# ESP32_MusicBox_using_Modules_2021-03-20.net
KiCad netlist of a schematic drawn in EasyEDA
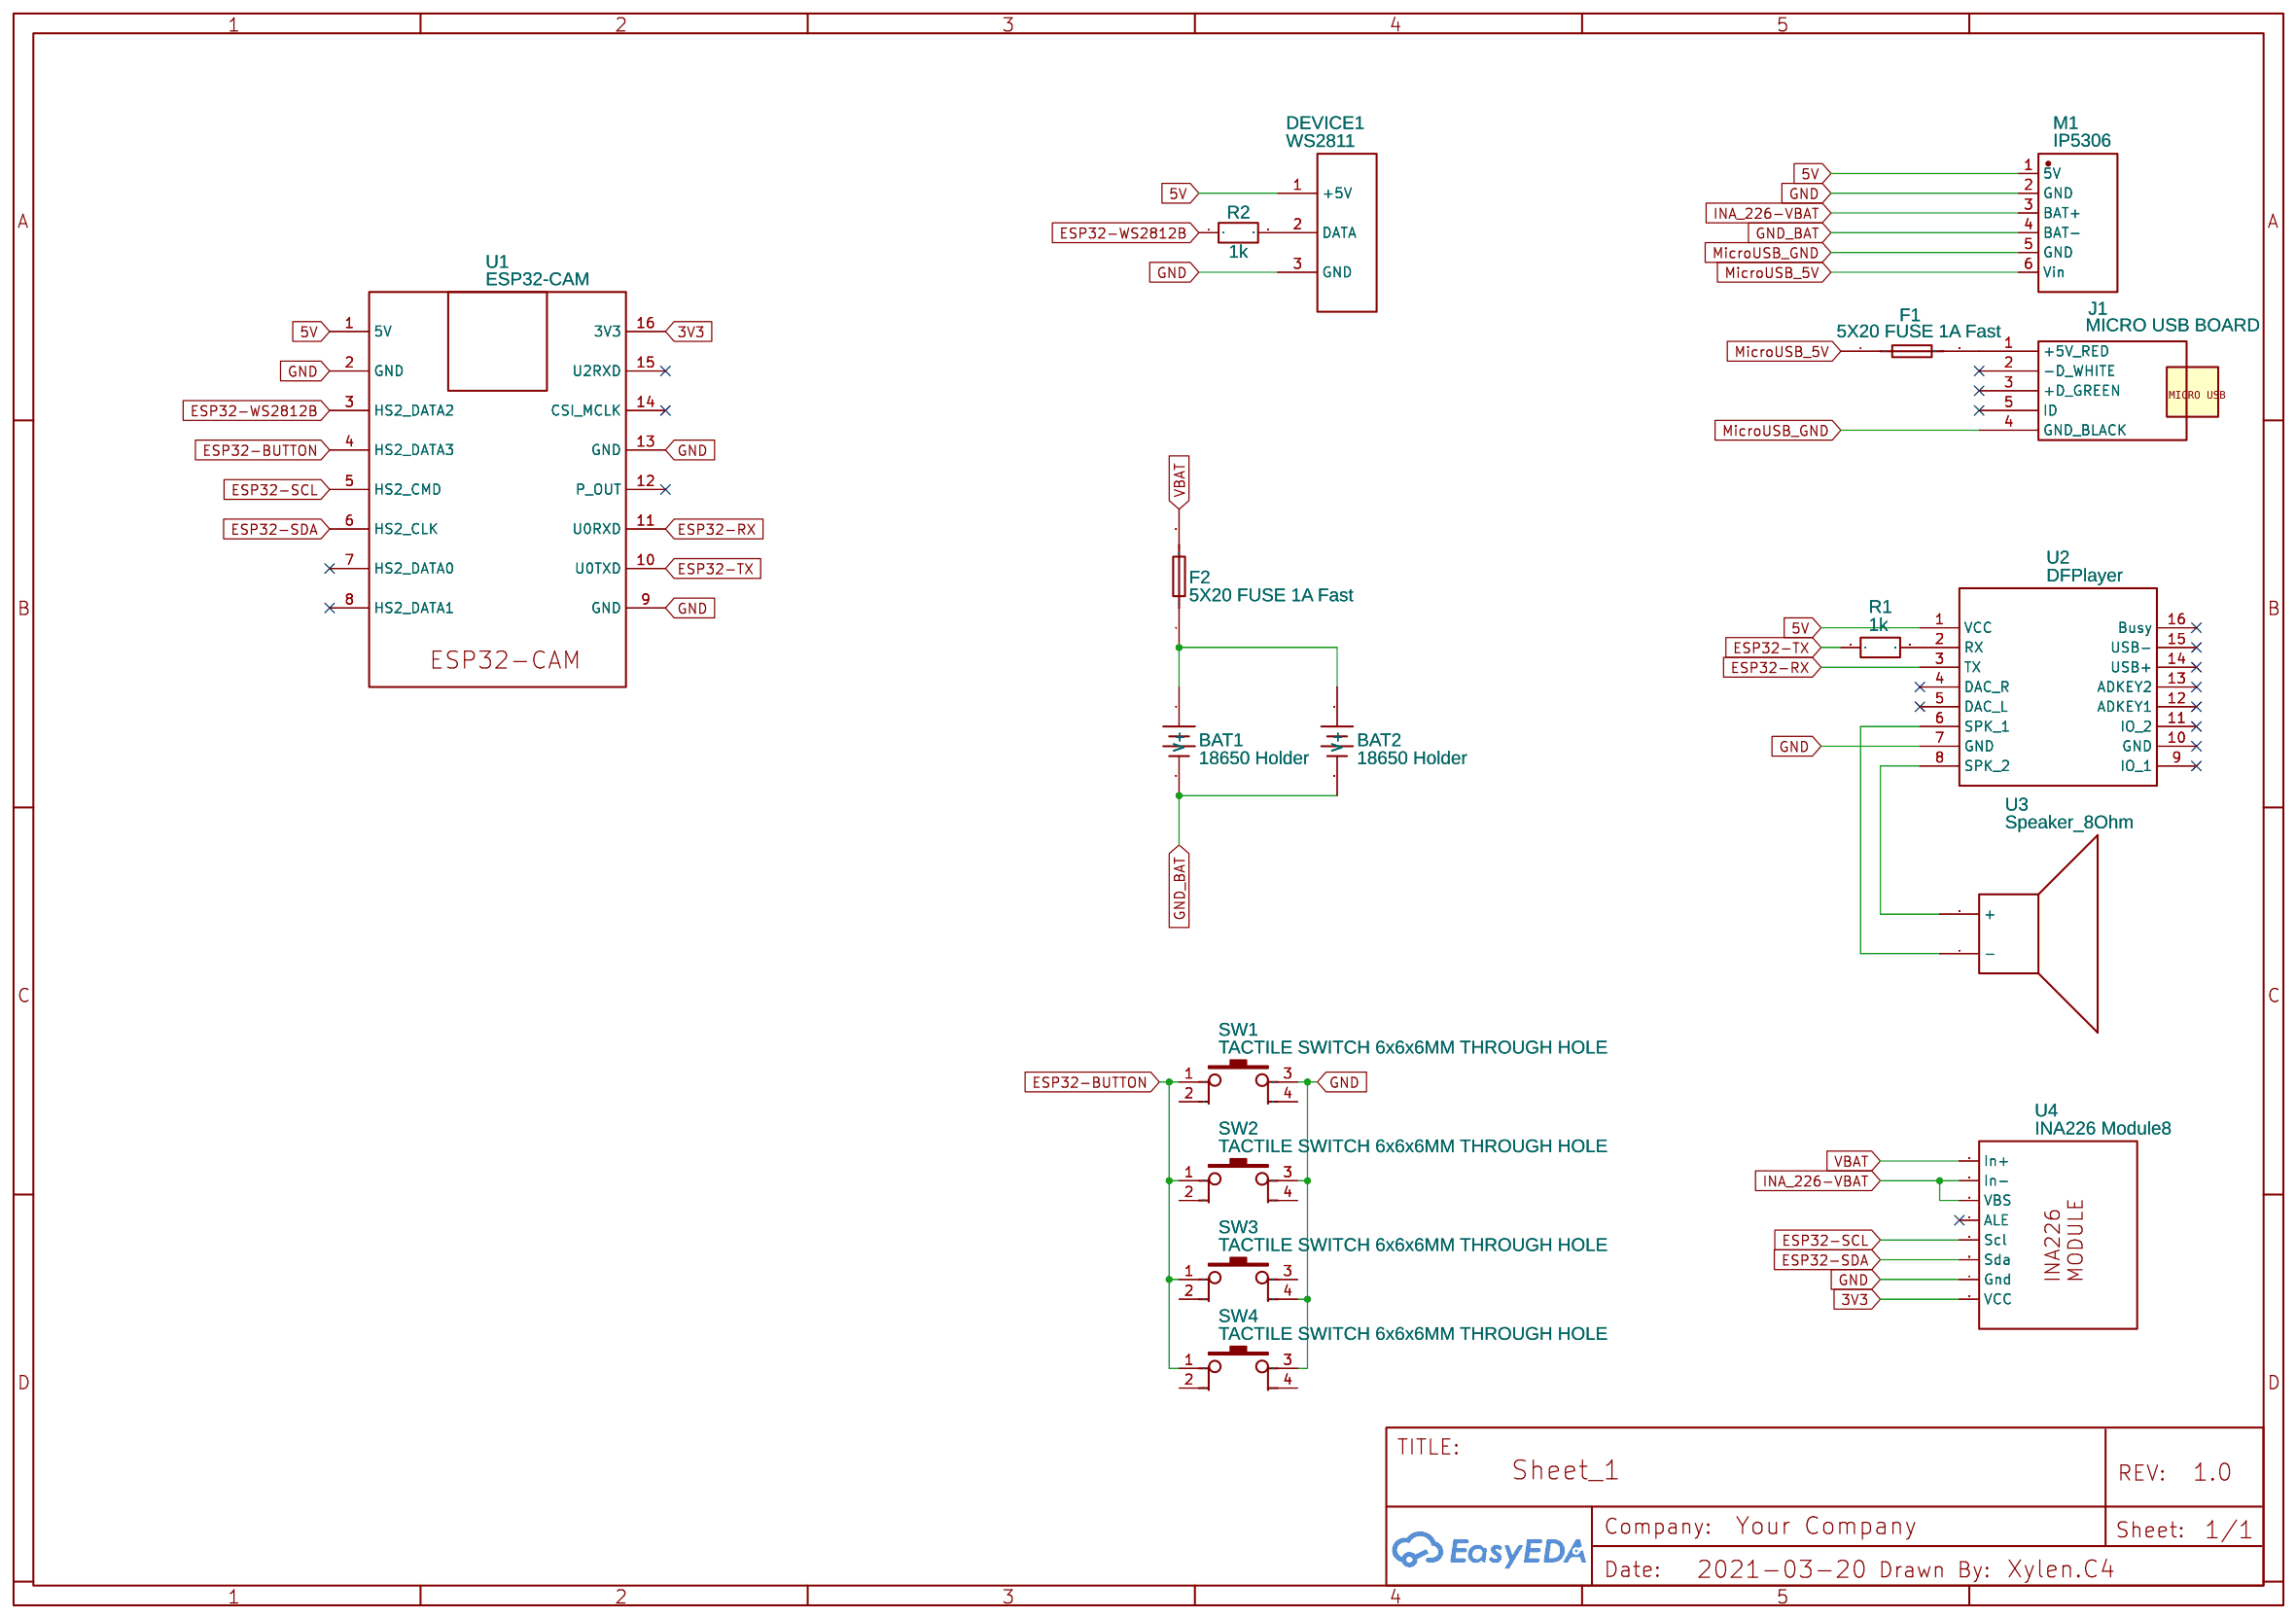
[diagram p0: schematic sheet]

(export (version "E")
  (design (tool "Eeschema 10.0.6"))
  (components
    (comp (ref "BAT1") (value "18650 Holder") (libsource (lib "") (part "18650 Holder")))
    (comp (ref "BAT2") (value "18650 Holder") (libsource (lib "") (part "18650 Holder")))
    (comp (ref "DEVICE1")
      (value "WS2811")
      (fields (field (name "BOM_Manufacturer Part") "WS2811 STRING"))
      (libsource (lib "") (part "WS2811"))
    )
    (comp (ref "F1")
      (value "5X20 FUSE 1A Fast")
      (fields
        (field (name "BOM_Manufacturer Part") "5x20 BLX-Atype Fuse holder XC-7")
        (field (name "BOM_Supplier Part") "C3131")
      )
      (libsource (lib "") (part "5X20 FUSE"))
    )
    (comp (ref "F2")
      (value "5X20 FUSE 1A Fast")
      (fields
        (field (name "BOM_Manufacturer Part") "5x20 BLX-Atype Fuse holder XC-7")
        (field (name "BOM_Supplier Part") "C3131")
      )
      (libsource (lib "") (part "5X20 FUSE_1"))
    )
    (comp (ref "J1") (value "MICRO USB BOARD") (libsource (lib "") (part "MICRO USB BOARD")))
    (comp (ref "M1")
      (value "IP5306")
      (fields
        (field (name "BOM_Manufacturer Part") "IP5306 Module")
        (field (name "BOM_Supplier Part") "IP5306Mod")
      )
      (libsource (lib "") (part "IP5306"))
    )
    (comp (ref "R1") (value "1k") (libsource (lib "") (part "R_AXIAL-0.5_EU")))
    (comp (ref "R2") (value "1k") (libsource (lib "") (part "R_AXIAL-0.5_EU")))
    (comp (ref "SW1")
      (value "TACTILE SWITCH 6x6x6MM THROUGH HOLE")
      (fields
        (field (name "BOM_Manufacturer Part") "SMD Tactile Switch6*6*6mm")
        (field (name "BOM_Supplier Part") "C23873")
      )
      (libsource (lib "") (part "TACTILE SWITCH 6x6x6MM THROUGH HOLE"))
    )
    (comp (ref "SW2")
      (value "TACTILE SWITCH 6x6x6MM THROUGH HOLE")
      (fields
        (field (name "BOM_Manufacturer Part") "SMD Tactile Switch6*6*6mm")
        (field (name "BOM_Supplier Part") "C23873")
      )
      (libsource (lib "") (part "TACTILE SWITCH 6x6x6MM THROUGH HOLE"))
    )
    (comp (ref "SW3")
      (value "TACTILE SWITCH 6x6x6MM THROUGH HOLE")
      (fields
        (field (name "BOM_Manufacturer Part") "SMD Tactile Switch6*6*6mm")
        (field (name "BOM_Supplier Part") "C23873")
      )
      (libsource (lib "") (part "TACTILE SWITCH 6x6x6MM THROUGH HOLE"))
    )
    (comp (ref "SW4")
      (value "TACTILE SWITCH 6x6x6MM THROUGH HOLE")
      (fields
        (field (name "BOM_Manufacturer Part") "SMD Tactile Switch6*6*6mm")
        (field (name "BOM_Supplier Part") "C23873")
      )
      (libsource (lib "") (part "TACTILE SWITCH 6x6x6MM THROUGH HOLE"))
    )
    (comp (ref "U1")
      (value "ESP32-CAM")
      (fields (field (name "BOM_Supplier Part") "1394679"))
      (libsource (lib "") (part "ESP32-CAM"))
    )
    (comp (ref "U2") (value "DFPlayer") (libsource (lib "") (part "DFPlayer")))
    (comp (ref "U3")
      (value "Speaker_8Ohm")
      (fields (field (name "BOM_Manufacturer Part") "Speaker"))
      (libsource (lib "") (part "Speaker_8Ohm"))
    )
    (comp (ref "U4")
      (value "INA226 Module8")
      (fields
        (field (name "BOM_Manufacturer Part") "INA226")
        (field (name "BOM_Supplier Part") "INA226 MODULE")
      )
      (libsource (lib "") (part "INA226 Module8"))
    )
  )
  (nets
    (net (code "1") (name "3V3") (class "Default")
      (node (ref "U1") (pin "16") (pinfunction "3V3_16") (pintype "unspecified"))
      (node (ref "U4") (pin "8") (pinfunction "VCC_8") (pintype "unspecified"))
    )
    (net (code "2") (name "5V") (class "Default")
      (node (ref "DEVICE1") (pin "1") (pinfunction "+5V_1") (pintype "unspecified"))
      (node (ref "M1") (pin "1") (pinfunction "5V_1") (pintype "unspecified"))
      (node (ref "U1") (pin "1") (pinfunction "5V_1") (pintype "unspecified"))
      (node (ref "U2") (pin "1") (pinfunction "VCC_1") (pintype "unspecified"))
    )
    (net (code "3") (name "ESP32-BUTTON") (class "Default")
      (node (ref "SW1") (pin "1") (pinfunction "1_1") (pintype "input"))
      (node (ref "SW2") (pin "1") (pinfunction "1_1") (pintype "input"))
      (node (ref "SW3") (pin "1") (pinfunction "1_1") (pintype "input"))
      (node (ref "SW4") (pin "1") (pinfunction "1_1") (pintype "input"))
      (node (ref "U1") (pin "4") (pinfunction "HS2_DATA3_4") (pintype "unspecified"))
    )
    (net (code "4") (name "ESP32-RX") (class "Default")
      (node (ref "U1") (pin "11") (pinfunction "U0RXD_11") (pintype "unspecified"))
      (node (ref "U2") (pin "3") (pinfunction "TX_3") (pintype "unspecified"))
    )
    (net (code "5") (name "ESP32-SCL") (class "Default")
      (node (ref "U1") (pin "5") (pinfunction "HS2_CMD_5") (pintype "unspecified"))
      (node (ref "U4") (pin "5") (pinfunction "Scl_5") (pintype "unspecified"))
    )
    (net (code "6") (name "ESP32-SDA") (class "Default")
      (node (ref "U1") (pin "6") (pinfunction "HS2_CLK_6") (pintype "unspecified"))
      (node (ref "U4") (pin "6") (pinfunction "Sda_6") (pintype "unspecified"))
    )
    (net (code "7") (name "ESP32-TX") (class "Default")
      (node (ref "R1") (pin "1") (pinfunction "1_1") (pintype "unspecified"))
      (node (ref "U1") (pin "10") (pinfunction "U0TXD_10") (pintype "unspecified"))
    )
    (net (code "8") (name "ESP32-WS2812B") (class "Default")
      (node (ref "R2") (pin "1") (pinfunction "1_1") (pintype "unspecified"))
      (node (ref "U1") (pin "3") (pinfunction "HS2_DATA2_3") (pintype "unspecified"))
    )
    (net (code "9") (name "GND") (class "Default")
      (node (ref "DEVICE1") (pin "3") (pinfunction "GND_3") (pintype "unspecified"))
      (node (ref "M1") (pin "2") (pinfunction "GND_2") (pintype "unspecified"))
      (node (ref "SW1") (pin "3") (pinfunction "3_3") (pintype "input"))
      (node (ref "SW2") (pin "3") (pinfunction "3_3") (pintype "input"))
      (node (ref "SW3") (pin "4") (pinfunction "4_4") (pintype "input"))
      (node (ref "SW4") (pin "3") (pinfunction "3_3") (pintype "input"))
      (node (ref "U1") (pin "13") (pinfunction "GND_13") (pintype "unspecified"))
      (node (ref "U1") (pin "2") (pinfunction "GND_2") (pintype "unspecified"))
      (node (ref "U1") (pin "9") (pinfunction "GND_9") (pintype "unspecified"))
      (node (ref "U2") (pin "7") (pinfunction "GND_7") (pintype "unspecified"))
      (node (ref "U4") (pin "7") (pinfunction "Gnd_7") (pintype "unspecified"))
    )
    (net (code "10") (name "GND_BAT") (class "Default")
      (node (ref "BAT1") (pin "2") (pinfunction "V-_2") (pintype "unspecified"))
      (node (ref "BAT2") (pin "2") (pinfunction "V-_2") (pintype "unspecified"))
      (node (ref "M1") (pin "4") (pinfunction "BAT-_4") (pintype "unspecified"))
    )
    (net (code "11") (name "INA_226-VBAT") (class "Default")
      (node (ref "M1") (pin "3") (pinfunction "BAT+_3") (pintype "unspecified"))
      (node (ref "U4") (pin "2") (pinfunction "In-_2") (pintype "unspecified"))
      (node (ref "U4") (pin "3") (pinfunction "VBS_3") (pintype "unspecified"))
    )
    (net (code "12") (name "MicroUSB_5V") (class "Default")
      (node (ref "F1") (pin "1") (pinfunction "1_1") (pintype "unspecified"))
      (node (ref "M1") (pin "6") (pinfunction "Vin_6") (pintype "unspecified"))
    )
    (net (code "13") (name "MicroUSB_GND") (class "Default")
      (node (ref "J1") (pin "4") (pinfunction "GND_BLACK_4") (pintype "bidirectional"))
      (node (ref "M1") (pin "5") (pinfunction "GND_5") (pintype "unspecified"))
    )
    (net (code "14") (name "Net-(BAT1-V+)") (class "Default")
      (node (ref "BAT1") (pin "1") (pinfunction "V+_1") (pintype "unspecified"))
      (node (ref "BAT2") (pin "1") (pinfunction "V+_1") (pintype "unspecified"))
      (node (ref "F2") (pin "1") (pinfunction "1_1") (pintype "unspecified"))
    )
    (net (code "15") (name "Net-(DEVICE1-DATA)") (class "Default")
      (node (ref "DEVICE1") (pin "2") (pinfunction "DATA_2") (pintype "unspecified"))
      (node (ref "R2") (pin "2") (pinfunction "2_2") (pintype "unspecified"))
    )
    (net (code "16") (name "Net-(J1-+5V_RED)") (class "Default")
      (node (ref "F1") (pin "2") (pinfunction "2_2") (pintype "unspecified"))
      (node (ref "J1") (pin "1") (pinfunction "+5V_RED_1") (pintype "bidirectional"))
    )
    (net (code "17") (name "Net-(U2-RX)") (class "Default")
      (node (ref "R1") (pin "2") (pinfunction "2_2") (pintype "unspecified"))
      (node (ref "U2") (pin "2") (pinfunction "RX_2") (pintype "unspecified"))
    )
    (net (code "18") (name "Net-(U2-SPK_1)") (class "Default")
      (node (ref "U2") (pin "6") (pinfunction "SPK_1_6") (pintype "unspecified"))
      (node (ref "U3") (pin "1") (pinfunction "-_1") (pintype "unspecified"))
    )
    (net (code "19") (name "Net-(U2-SPK_2)") (class "Default")
      (node (ref "U2") (pin "8") (pinfunction "SPK_2_8") (pintype "unspecified"))
      (node (ref "U3") (pin "2") (pinfunction "+_2") (pintype "unspecified"))
    )
    (net (code "20") (name "VBAT") (class "Default")
      (node (ref "F2") (pin "2") (pinfunction "2_2") (pintype "unspecified"))
      (node (ref "U4") (pin "1") (pinfunction "In+_1") (pintype "unspecified"))
    )
    (net (code "21") (name "unconnected-(J1-+D_GREEN-Pad3)") (class "Default")
      (node (ref "J1") (pin "3") (pinfunction "+D_GREEN_3") (pintype "bidirectional+no_connect"))
    )
    (net (code "22") (name "unconnected-(J1--D_WHITE-Pad2)") (class "Default")
      (node (ref "J1") (pin "2") (pinfunction "-D_WHITE_2") (pintype "bidirectional+no_connect"))
    )
    (net (code "23") (name "unconnected-(J1-ID-Pad5)") (class "Default")
      (node (ref "J1") (pin "5") (pinfunction "ID_5") (pintype "bidirectional+no_connect"))
    )
    (net (code "24") (name "unconnected-(SW1-Pad2)") (class "Default")
      (node (ref "SW1") (pin "2") (pinfunction "2_2") (pintype "input"))
    )
    (net (code "25") (name "unconnected-(SW1-Pad4)") (class "Default")
      (node (ref "SW1") (pin "4") (pinfunction "4_4") (pintype "input"))
    )
    (net (code "26") (name "unconnected-(SW2-Pad2)") (class "Default")
      (node (ref "SW2") (pin "2") (pinfunction "2_2") (pintype "input"))
    )
    (net (code "27") (name "unconnected-(SW2-Pad4)") (class "Default")
      (node (ref "SW2") (pin "4") (pinfunction "4_4") (pintype "input"))
    )
    (net (code "28") (name "unconnected-(SW3-Pad2)") (class "Default")
      (node (ref "SW3") (pin "2") (pinfunction "2_2") (pintype "input"))
    )
    (net (code "29") (name "unconnected-(SW3-Pad3)") (class "Default")
      (node (ref "SW3") (pin "3") (pinfunction "3_3") (pintype "input"))
    )
    (net (code "30") (name "unconnected-(SW4-Pad2)") (class "Default")
      (node (ref "SW4") (pin "2") (pinfunction "2_2") (pintype "input"))
    )
    (net (code "31") (name "unconnected-(SW4-Pad4)") (class "Default")
      (node (ref "SW4") (pin "4") (pinfunction "4_4") (pintype "input"))
    )
    (net (code "32") (name "unconnected-(U1-CSI_MCLK-Pad14)") (class "Default")
      (node (ref "U1") (pin "14") (pinfunction "CSI_MCLK_14") (pintype "unspecified+no_connect"))
    )
    (net (code "33") (name "unconnected-(U1-HS2_DATA0-Pad7)") (class "Default")
      (node (ref "U1") (pin "7") (pinfunction "HS2_DATA0_7") (pintype "unspecified+no_connect"))
    )
    (net (code "34") (name "unconnected-(U1-HS2_DATA1-Pad8)") (class "Default")
      (node (ref "U1") (pin "8") (pinfunction "HS2_DATA1_8") (pintype "unspecified+no_connect"))
    )
    (net (code "35") (name "unconnected-(U1-P_OUT-Pad12)") (class "Default")
      (node (ref "U1") (pin "12") (pinfunction "P_OUT_12") (pintype "unspecified+no_connect"))
    )
    (net (code "36") (name "unconnected-(U1-U2RXD-Pad15)") (class "Default")
      (node (ref "U1") (pin "15") (pinfunction "U2RXD_15") (pintype "unspecified+no_connect"))
    )
    (net (code "37") (name "unconnected-(U2-ADKEY1-Pad12)") (class "Default")
      (node (ref "U2") (pin "12") (pinfunction "ADKEY1_12") (pintype "unspecified+no_connect"))
    )
    (net (code "38") (name "unconnected-(U2-ADKEY2-Pad13)") (class "Default")
      (node (ref "U2") (pin "13") (pinfunction "ADKEY2_13") (pintype "unspecified+no_connect"))
    )
    (net (code "39") (name "unconnected-(U2-Busy-Pad16)") (class "Default")
      (node (ref "U2") (pin "16") (pinfunction "Busy_16") (pintype "unspecified+no_connect"))
    )
    (net (code "40") (name "unconnected-(U2-DAC_L-Pad5)") (class "Default")
      (node (ref "U2") (pin "5") (pinfunction "DAC_L_5") (pintype "unspecified+no_connect"))
    )
    (net (code "41") (name "unconnected-(U2-DAC_R-Pad4)") (class "Default")
      (node (ref "U2") (pin "4") (pinfunction "DAC_R_4") (pintype "unspecified+no_connect"))
    )
    (net (code "42") (name "unconnected-(U2-GND-Pad10)") (class "Default")
      (node (ref "U2") (pin "10") (pinfunction "GND_10") (pintype "unspecified+no_connect"))
    )
    (net (code "43") (name "unconnected-(U2-IO_1-Pad9)") (class "Default")
      (node (ref "U2") (pin "9") (pinfunction "IO_1_9") (pintype "unspecified+no_connect"))
    )
    (net (code "44") (name "unconnected-(U2-IO_2-Pad11)") (class "Default")
      (node (ref "U2") (pin "11") (pinfunction "IO_2_11") (pintype "unspecified+no_connect"))
    )
    (net (code "45") (name "unconnected-(U2-USB+-Pad14)") (class "Default")
      (node (ref "U2") (pin "14") (pinfunction "USB+_14") (pintype "unspecified+no_connect"))
    )
    (net (code "46") (name "unconnected-(U2-USB--Pad15)") (class "Default")
      (node (ref "U2") (pin "15") (pinfunction "USB-_15") (pintype "unspecified+no_connect"))
    )
    (net (code "47") (name "unconnected-(U4-ALE-Pad4)") (class "Default")
      (node (ref "U4") (pin "4") (pinfunction "ALE_4") (pintype "unspecified+no_connect"))
    )
  )
)
